# Multimeter1_1.net
KiCad netlist of a schematic drawn in EAGLE
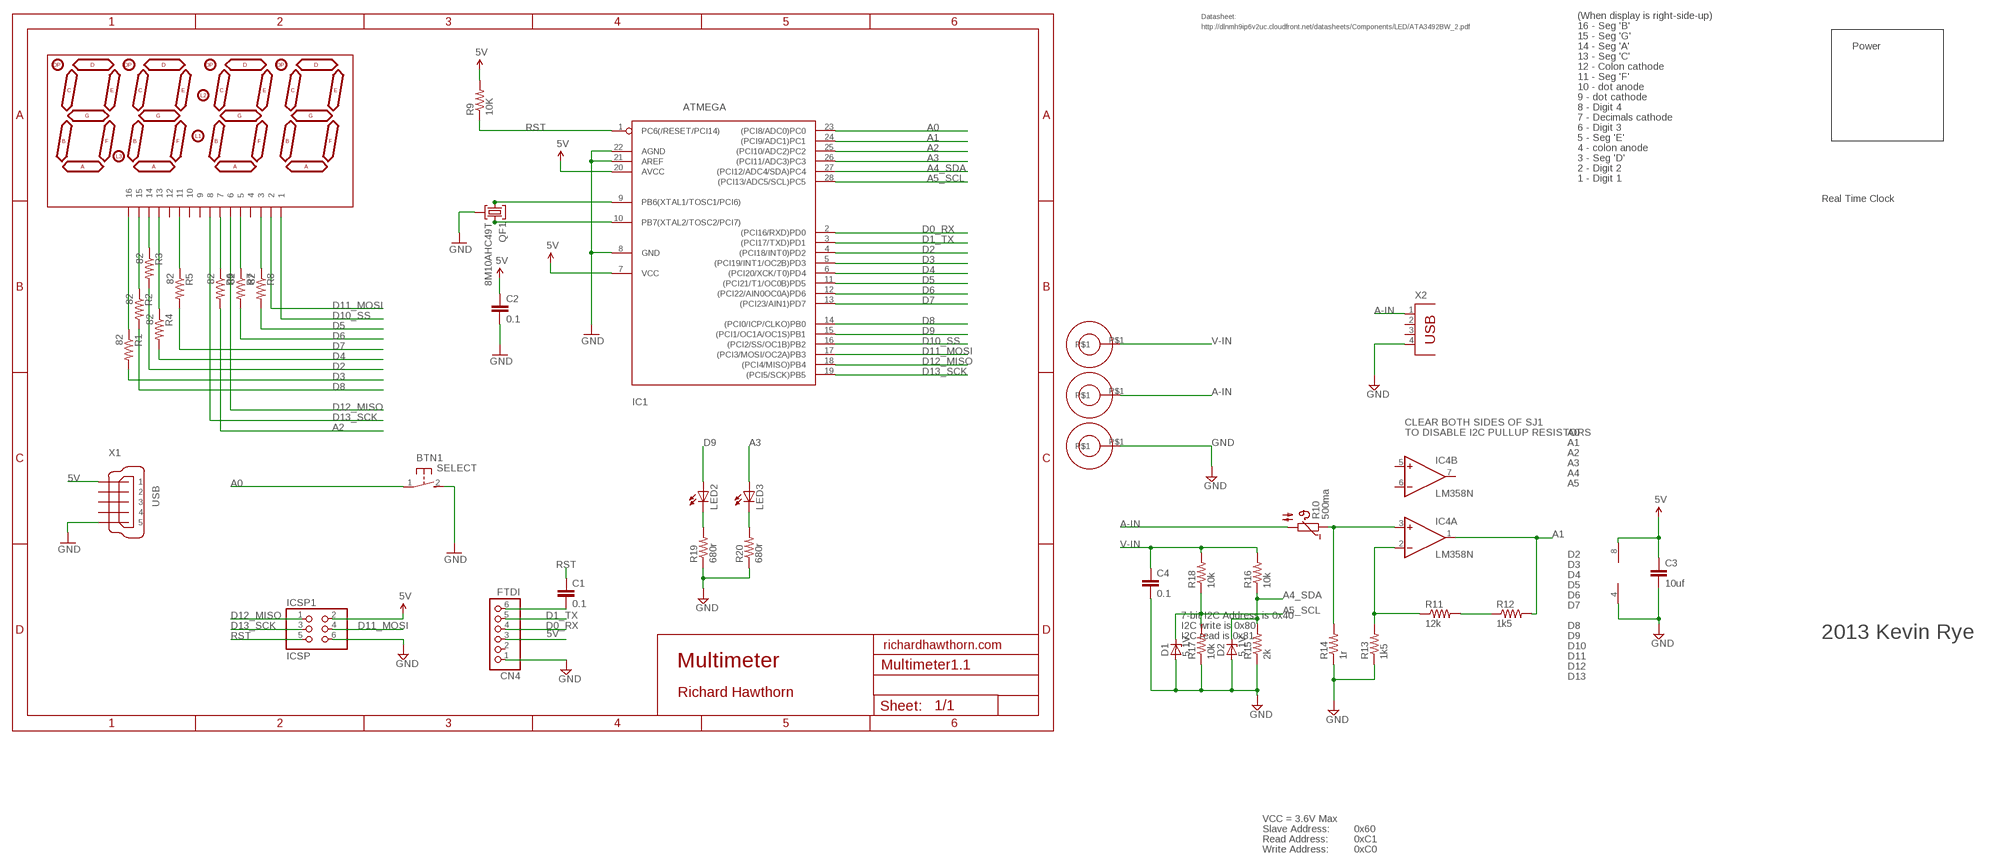
[diagram p0: schematic, sheet 1]

(export (version "E")
  (design (tool "Eeschema 10.0.6"))
  (components
    (comp (ref "BTN1")
      (value "SELECT")
      (footprint "eagle-import:DTS-3")
      (libsource (lib "eagle-import") (part "DTS-3"))
    )
    (comp (ref "C1")
      (value "0.1")
      (footprint "eagle-import:CAP-PTH-SMALL2")
      (libsource (lib "eagle-import") (part "CAPPTH2"))
    )
    (comp (ref "C2")
      (value "0.1")
      (footprint "eagle-import:CAP-PTH-SMALL2")
      (libsource (lib "eagle-import") (part "CAPPTH2"))
    )
    (comp (ref "C3")
      (value "10uf")
      (footprint "eagle-import:CAP-PTH-SMALL2")
      (libsource (lib "eagle-import") (part "CAPPTH2"))
    )
    (comp (ref "C4")
      (value "0.1")
      (footprint "eagle-import:CAP-PTH-SMALL2")
      (libsource (lib "eagle-import") (part "CAPPTH2"))
    )
    (comp (ref "CN4")
      (value "FTDI")
      (footprint "eagle-import:1X06")
      (libsource (lib "eagle-import") (part "PINHD-1X6"))
    )
    (comp (ref "D1")
      (value "5.1V")
      (footprint "eagle-import:DO34Z7")
      (libsource (lib "eagle-import") (part "BZX90"))
    )
    (comp (ref "D2")
      (value "5.1V")
      (footprint "eagle-import:DO34Z7")
      (libsource (lib "eagle-import") (part "BZX90"))
    )
    (comp (ref "IC1")
      (value "ATMEGA")
      (footprint "eagle-import:DIL28-3-ROUND")
      (libsource (lib "eagle-import") (part "ATMEGA168PROUND"))
    )
    (comp (ref "IC4")
      (value "LM358N")
      (footprint "eagle-import:DIL08")
      (libsource (lib "eagle-import") (part "LM358N"))
    )
    (comp (ref "ICSP1")
      (value "ICSP")
      (footprint "eagle-import:2X03")
      (libsource (lib "eagle-import") (part "PINHD-2X3"))
    )
    (comp (ref "LED1")
      (value "7SEG-4DIGIT")
      (footprint "eagle-import:SPARKFUN_7-SEGMENT-4DIGIT")
      (libsource (lib "eagle-import") (part "7SEG-4DIGIT"))
    )
    (comp (ref "LED2")
      (value "LED5MM")
      (footprint "eagle-import:LED5MM")
      (libsource (lib "eagle-import") (part "LED5MM"))
    )
    (comp (ref "LED3")
      (value "LED5MM")
      (footprint "eagle-import:LED5MM")
      (libsource (lib "eagle-import") (part "LED5MM"))
    )
    (comp (ref "QF1")
      (value "8M10AHC49T")
      (footprint "eagle-import:HC49U")
      (libsource (lib "eagle-import") (part "8M10AHC49T"))
    )
    (comp (ref "R1")
      (value "82")
      (footprint "eagle-import:0204_7")
      (libsource (lib "eagle-import") (part "R-US_0204/7"))
    )
    (comp (ref "R2")
      (value "82")
      (footprint "eagle-import:0204_7")
      (libsource (lib "eagle-import") (part "R-US_0204/7"))
    )
    (comp (ref "R3")
      (value "82")
      (footprint "eagle-import:0204_7")
      (libsource (lib "eagle-import") (part "R-US_0204/7"))
    )
    (comp (ref "R4")
      (value "82")
      (footprint "eagle-import:0204_7")
      (libsource (lib "eagle-import") (part "R-US_0204/7"))
    )
    (comp (ref "R5")
      (value "82")
      (footprint "eagle-import:0204_7")
      (libsource (lib "eagle-import") (part "R-US_0204/7"))
    )
    (comp (ref "R6")
      (value "82")
      (footprint "eagle-import:0204_7")
      (libsource (lib "eagle-import") (part "R-US_0204/7"))
    )
    (comp (ref "R7")
      (value "82")
      (footprint "eagle-import:0204_7")
      (libsource (lib "eagle-import") (part "R-US_0204/7"))
    )
    (comp (ref "R8")
      (value "82")
      (footprint "eagle-import:0204_7")
      (libsource (lib "eagle-import") (part "R-US_0204/7"))
    )
    (comp (ref "R9")
      (value "10K")
      (footprint "eagle-import:0204_7")
      (libsource (lib "eagle-import") (part "R-US_0204/7"))
    )
    (comp (ref "R10")
      (value "500ma")
      (footprint "eagle-import:B57164")
      (fields (field (name "MPN") "B57164K474K52"))
      (libsource (lib "eagle-import") (part "B57164"))
    )
    (comp (ref "R11")
      (value "12k")
      (footprint "eagle-import:0204_7")
      (libsource (lib "eagle-import") (part "R-US_0204/7"))
    )
    (comp (ref "R12")
      (value "1k5")
      (footprint "eagle-import:0204_7")
      (libsource (lib "eagle-import") (part "R-US_0204/7"))
    )
    (comp (ref "R13")
      (value "1k5")
      (footprint "eagle-import:0204_7")
      (libsource (lib "eagle-import") (part "R-US_0204/7"))
    )
    (comp (ref "R14")
      (value "1r")
      (footprint "eagle-import:0204_7")
      (libsource (lib "eagle-import") (part "R-US_0204/7"))
    )
    (comp (ref "R15")
      (value "2k")
      (footprint "eagle-import:0204_7")
      (libsource (lib "eagle-import") (part "R-US_0204/7"))
    )
    (comp (ref "R16")
      (value "10k")
      (footprint "eagle-import:0204_7")
      (libsource (lib "eagle-import") (part "R-US_0204/7"))
    )
    (comp (ref "R17")
      (value "10k")
      (footprint "eagle-import:0204_7")
      (libsource (lib "eagle-import") (part "R-US_0204/7"))
    )
    (comp (ref "R18")
      (value "10k")
      (footprint "eagle-import:0204_7")
      (libsource (lib "eagle-import") (part "R-US_0204/7"))
    )
    (comp (ref "R19")
      (value "680r")
      (footprint "eagle-import:0204_7")
      (libsource (lib "eagle-import") (part "R-US_0204/7"))
    )
    (comp (ref "R20")
      (value "680r")
      (footprint "eagle-import:0204_7")
      (libsource (lib "eagle-import") (part "R-US_0204/7"))
    )
    (comp (ref "U$1")
      (value "BANANA")
      (footprint "eagle-import:BANANA")
      (libsource (lib "eagle-import") (part "BANANA"))
    )
    (comp (ref "U$5")
      (value "BANANA")
      (footprint "eagle-import:BANANA")
      (libsource (lib "eagle-import") (part "BANANA"))
    )
    (comp (ref "U$6")
      (value "BANANA")
      (footprint "eagle-import:BANANA")
      (libsource (lib "eagle-import") (part "BANANA"))
    )
    (comp (ref "X1")
      (value "USB")
      (footprint "eagle-import:32005-601")
      (libsource (lib "eagle-import") (part "MINI-USB_SHIELD5P2-32005-601"))
    )
    (comp (ref "X2")
      (value "PN87520")
      (footprint "eagle-import:PN87520")
      (libsource (lib "eagle-import") (part "PN87520"))
    )
  )
  (nets
    (net (code "1") (name "/A-IN") (class "Default")
      (node (ref "R10") (pin "2") (pinfunction "2_2") (pintype "passive"))
      (node (ref "U$5") (pin "P$1") (pinfunction "P$1_P$1") (pintype "bidirectional"))
      (node (ref "X2") (pin "1") (pinfunction "1_1") (pintype "passive"))
    )
    (net (code "2") (name "/A0") (class "Default")
      (node (ref "BTN1") (pin "1") (pinfunction "1_1") (pintype "passive"))
      (node (ref "IC1") (pin "23") (pinfunction "(PCI8/ADC0)PC0_23") (pintype "bidirectional"))
    )
    (net (code "3") (name "/A1") (class "Default")
      (node (ref "IC1") (pin "24") (pinfunction "(PCI9/ADC1)PC1_24") (pintype "bidirectional"))
      (node (ref "IC4") (pin "1") (pinfunction "OUT_1") (pintype "output"))
      (node (ref "R12") (pin "2") (pinfunction "2_2") (pintype "passive"))
    )
    (net (code "4") (name "/A2") (class "Default")
      (node (ref "IC1") (pin "25") (pinfunction "(PCI10/ADC2)PC2_25") (pintype "bidirectional"))
      (node (ref "R6") (pin "2") (pinfunction "2_2") (pintype "passive"))
    )
    (net (code "5") (name "/A3") (class "Default")
      (node (ref "IC1") (pin "26") (pinfunction "(PCI11/ADC3)PC3_26") (pintype "bidirectional"))
      (node (ref "LED3") (pin "A") (pinfunction "A_A") (pintype "passive"))
    )
    (net (code "6") (name "/A4_SDA") (class "Default")
      (node (ref "D2") (pin "C") (pinfunction "C_C") (pintype "passive"))
      (node (ref "IC1") (pin "27") (pinfunction "(PCI12/ADC4/SDA)PC4_27") (pintype "bidirectional"))
      (node (ref "R15") (pin "2") (pinfunction "2_2") (pintype "passive"))
      (node (ref "R16") (pin "1") (pinfunction "1_1") (pintype "passive"))
    )
    (net (code "7") (name "/A5_SCL") (class "Default")
      (node (ref "D1") (pin "C") (pinfunction "C_C") (pintype "passive"))
      (node (ref "IC1") (pin "28") (pinfunction "(PCI13/ADC5/SCL)PC5_28") (pintype "bidirectional"))
      (node (ref "R17") (pin "2") (pinfunction "2_2") (pintype "passive"))
      (node (ref "R18") (pin "1") (pinfunction "1_1") (pintype "passive"))
    )
    (net (code "8") (name "/D0_RX") (class "Default")
      (node (ref "CN4") (pin "4") (pinfunction "4_4") (pintype "passive"))
      (node (ref "IC1") (pin "2") (pinfunction "(PCI16/RXD)PD0_2") (pintype "bidirectional"))
    )
    (net (code "9") (name "/D1_TX") (class "Default")
      (node (ref "CN4") (pin "5") (pinfunction "5_5") (pintype "passive"))
      (node (ref "IC1") (pin "3") (pinfunction "(PCI17/TXD)PD1_3") (pintype "bidirectional"))
    )
    (net (code "10") (name "/D2") (class "Default")
      (node (ref "IC1") (pin "4") (pinfunction "(PCI18/INT0)PD2_4") (pintype "bidirectional"))
      (node (ref "R3") (pin "2") (pinfunction "2_2") (pintype "passive"))
    )
    (net (code "11") (name "/D3") (class "Default")
      (node (ref "IC1") (pin "5") (pinfunction "(PCI19/INT1/OC2B)PD3_5") (pintype "bidirectional"))
      (node (ref "R1") (pin "2") (pinfunction "2_2") (pintype "passive"))
    )
    (net (code "12") (name "/D4") (class "Default")
      (node (ref "IC1") (pin "6") (pinfunction "(PCI20/XCK/T0)PD4_6") (pintype "bidirectional"))
      (node (ref "R4") (pin "2") (pinfunction "2_2") (pintype "passive"))
    )
    (net (code "13") (name "/D5") (class "Default")
      (node (ref "IC1") (pin "11") (pinfunction "(PCI21/T1/OC0B)PD5_11") (pintype "bidirectional"))
      (node (ref "R8") (pin "2") (pinfunction "2_2") (pintype "passive"))
    )
    (net (code "14") (name "/D6") (class "Default")
      (node (ref "IC1") (pin "12") (pinfunction "(PCI22/AIN0OC0A)PD6_12") (pintype "bidirectional"))
      (node (ref "R7") (pin "2") (pinfunction "2_2") (pintype "passive"))
    )
    (net (code "15") (name "/D7") (class "Default")
      (node (ref "IC1") (pin "13") (pinfunction "(PCI23/AIN1)PD7_13") (pintype "bidirectional"))
      (node (ref "R5") (pin "2") (pinfunction "2_2") (pintype "passive"))
    )
    (net (code "16") (name "/D8") (class "Default")
      (node (ref "IC1") (pin "14") (pinfunction "(PCI0/ICP/CLKO)PB0_14") (pintype "bidirectional"))
      (node (ref "R2") (pin "2") (pinfunction "2_2") (pintype "passive"))
    )
    (net (code "17") (name "/D9") (class "Default")
      (node (ref "IC1") (pin "15") (pinfunction "(PCI1/OC1A/OC1S)PB1_15") (pintype "bidirectional"))
      (node (ref "LED2") (pin "A") (pinfunction "A_A") (pintype "passive"))
    )
    (net (code "18") (name "/D10_SS") (class "Default")
      (node (ref "IC1") (pin "16") (pinfunction "(PCI2/SS/OC1B)PB2_16") (pintype "bidirectional"))
      (node (ref "LED1") (pin "1") (pinfunction "1_1") (pintype "bidirectional"))
    )
    (net (code "19") (name "/D11_MOSI") (class "Default")
      (node (ref "IC1") (pin "17") (pinfunction "(PCI3/MOSI/OC2A)PB3_17") (pintype "bidirectional"))
      (node (ref "ICSP1") (pin "4") (pinfunction "4_4") (pintype "passive"))
      (node (ref "LED1") (pin "2") (pinfunction "2_2") (pintype "bidirectional"))
    )
    (net (code "20") (name "/D12_MISO") (class "Default")
      (node (ref "IC1") (pin "18") (pinfunction "(PCI4/MISO)PB4_18") (pintype "bidirectional"))
      (node (ref "ICSP1") (pin "1") (pinfunction "1_1") (pintype "passive"))
      (node (ref "LED1") (pin "6") (pinfunction "6_6") (pintype "bidirectional"))
    )
    (net (code "21") (name "/D13_SCK") (class "Default")
      (node (ref "IC1") (pin "19") (pinfunction "(PCI5/SCK)PB5_19") (pintype "bidirectional"))
      (node (ref "ICSP1") (pin "3") (pinfunction "3_3") (pintype "passive"))
      (node (ref "LED1") (pin "8") (pinfunction "8_8") (pintype "bidirectional"))
    )
    (net (code "22") (name "/RST") (class "Default")
      (node (ref "C1") (pin "1") (pinfunction "1_1") (pintype "passive"))
      (node (ref "IC1") (pin "1") (pinfunction "PC6(/RESET/PCI14)_1") (pintype "bidirectional"))
      (node (ref "ICSP1") (pin "5") (pinfunction "5_5") (pintype "passive"))
      (node (ref "R9") (pin "1") (pinfunction "1_1") (pintype "passive"))
    )
    (net (code "23") (name "/V-IN") (class "Default")
      (node (ref "C4") (pin "1") (pinfunction "1_1") (pintype "passive"))
      (node (ref "R16") (pin "2") (pinfunction "2_2") (pintype "passive"))
      (node (ref "R18") (pin "2") (pinfunction "2_2") (pintype "passive"))
      (node (ref "U$1") (pin "P$1") (pinfunction "P$1_P$1") (pintype "bidirectional"))
    )
    (net (code "24") (name "5V") (class "Default")
      (node (ref "C2") (pin "1") (pinfunction "1_1") (pintype "passive"))
      (node (ref "C3") (pin "1") (pinfunction "1_1") (pintype "passive"))
      (node (ref "CN4") (pin "3") (pinfunction "3_3") (pintype "passive"))
      (node (ref "IC1") (pin "20") (pinfunction "AVCC_20") (pintype "bidirectional"))
      (node (ref "IC1") (pin "7") (pinfunction "VCC_7") (pintype "bidirectional"))
      (node (ref "IC4") (pin "8") (pinfunction "V+_8") (pintype "power_in"))
      (node (ref "ICSP1") (pin "2") (pinfunction "2_2") (pintype "passive"))
      (node (ref "R9") (pin "2") (pinfunction "2_2") (pintype "passive"))
      (node (ref "X1") (pin "1") (pinfunction "1_1") (pintype "passive"))
    )
    (net (code "25") (name "GND") (class "Default")
      (node (ref "BTN1") (pin "2") (pinfunction "2_2") (pintype "passive"))
      (node (ref "C2") (pin "2") (pinfunction "2_2") (pintype "passive"))
      (node (ref "C3") (pin "2") (pinfunction "2_2") (pintype "passive"))
      (node (ref "C4") (pin "2") (pinfunction "2_2") (pintype "passive"))
      (node (ref "CN4") (pin "1") (pinfunction "1_1") (pintype "passive"))
      (node (ref "D1") (pin "A") (pinfunction "A_A") (pintype "passive"))
      (node (ref "D2") (pin "A") (pinfunction "A_A") (pintype "passive"))
      (node (ref "IC1") (pin "21") (pinfunction "AREF_21") (pintype "bidirectional"))
      (node (ref "IC1") (pin "22") (pinfunction "AGND_22") (pintype "bidirectional"))
      (node (ref "IC1") (pin "8") (pinfunction "GND_8") (pintype "bidirectional"))
      (node (ref "IC4") (pin "4") (pinfunction "V-_4") (pintype "power_in"))
      (node (ref "ICSP1") (pin "6") (pinfunction "6_6") (pintype "passive"))
      (node (ref "QF1") (pin "2") (pinfunction "2_2") (pintype "passive"))
      (node (ref "R13") (pin "1") (pinfunction "1_1") (pintype "passive"))
      (node (ref "R14") (pin "1") (pinfunction "1_1") (pintype "passive"))
      (node (ref "R15") (pin "1") (pinfunction "1_1") (pintype "passive"))
      (node (ref "R17") (pin "1") (pinfunction "1_1") (pintype "passive"))
      (node (ref "R19") (pin "1") (pinfunction "1_1") (pintype "passive"))
      (node (ref "R20") (pin "1") (pinfunction "1_1") (pintype "passive"))
      (node (ref "U$6") (pin "P$1") (pinfunction "P$1_P$1") (pintype "bidirectional"))
      (node (ref "X1") (pin "5") (pinfunction "5_5") (pintype "passive"))
      (node (ref "X2") (pin "4") (pinfunction "4_4") (pintype "passive"))
    )
    (net (code "26") (name "Net-(C1-Pad2)") (class "Default")
      (node (ref "C1") (pin "2") (pinfunction "2_2") (pintype "passive"))
      (node (ref "CN4") (pin "6") (pinfunction "6_6") (pintype "passive"))
    )
    (net (code "27") (name "Net-(IC1-PB6(XTAL1{slash}TOSC1{slash}PCI6))") (class "Default")
      (node (ref "IC1") (pin "9") (pinfunction "PB6(XTAL1/TOSC1/PCI6)_9") (pintype "bidirectional"))
      (node (ref "QF1") (pin "1") (pinfunction "1_1") (pintype "passive"))
    )
    (net (code "28") (name "Net-(IC1-PB7(XTAL2{slash}TOSC2{slash}PCI7))") (class "Default")
      (node (ref "IC1") (pin "10") (pinfunction "PB7(XTAL2/TOSC2/PCI7)_10") (pintype "bidirectional"))
      (node (ref "QF1") (pin "3") (pinfunction "3_3") (pintype "passive"))
    )
    (net (code "29") (name "Net-(IC4A-+IN)") (class "Default")
      (node (ref "IC4") (pin "3") (pinfunction "+IN_3") (pintype "input"))
      (node (ref "R10") (pin "1") (pinfunction "1_1") (pintype "passive"))
      (node (ref "R14") (pin "2") (pinfunction "2_2") (pintype "passive"))
    )
    (net (code "30") (name "Net-(IC4A--IN)") (class "Default")
      (node (ref "IC4") (pin "2") (pinfunction "-IN_2") (pintype "input"))
      (node (ref "R11") (pin "1") (pinfunction "1_1") (pintype "passive"))
      (node (ref "R13") (pin "2") (pinfunction "2_2") (pintype "passive"))
    )
    (net (code "31") (name "Net-(LED1-Pad3)") (class "Default")
      (node (ref "LED1") (pin "3") (pinfunction "3_3") (pintype "bidirectional"))
      (node (ref "R8") (pin "1") (pinfunction "1_1") (pintype "passive"))
    )
    (net (code "32") (name "Net-(LED1-Pad5)") (class "Default")
      (node (ref "LED1") (pin "5") (pinfunction "5_5") (pintype "bidirectional"))
      (node (ref "R7") (pin "1") (pinfunction "1_1") (pintype "passive"))
    )
    (net (code "33") (name "Net-(LED1-Pad7)") (class "Default")
      (node (ref "LED1") (pin "7") (pinfunction "7_7") (pintype "bidirectional"))
      (node (ref "R6") (pin "1") (pinfunction "1_1") (pintype "passive"))
    )
    (net (code "34") (name "Net-(LED1-Pad11)") (class "Default")
      (node (ref "LED1") (pin "11") (pinfunction "11_11") (pintype "bidirectional"))
      (node (ref "R5") (pin "1") (pinfunction "1_1") (pintype "passive"))
    )
    (net (code "35") (name "Net-(LED1-Pad13)") (class "Default")
      (node (ref "LED1") (pin "13") (pinfunction "13_13") (pintype "bidirectional"))
      (node (ref "R4") (pin "1") (pinfunction "1_1") (pintype "passive"))
    )
    (net (code "36") (name "Net-(LED1-Pad14)") (class "Default")
      (node (ref "LED1") (pin "14") (pinfunction "14_14") (pintype "bidirectional"))
      (node (ref "R3") (pin "1") (pinfunction "1_1") (pintype "passive"))
    )
    (net (code "37") (name "Net-(LED1-Pad15)") (class "Default")
      (node (ref "LED1") (pin "15") (pinfunction "15_15") (pintype "bidirectional"))
      (node (ref "R2") (pin "1") (pinfunction "1_1") (pintype "passive"))
    )
    (net (code "38") (name "Net-(LED1-Pad16)") (class "Default")
      (node (ref "LED1") (pin "16") (pinfunction "16_16") (pintype "bidirectional"))
      (node (ref "R1") (pin "1") (pinfunction "1_1") (pintype "passive"))
    )
    (net (code "39") (name "Net-(LED2-C)") (class "Default")
      (node (ref "LED2") (pin "K") (pinfunction "C_K") (pintype "passive"))
      (node (ref "R19") (pin "2") (pinfunction "2_2") (pintype "passive"))
    )
    (net (code "40") (name "Net-(LED3-C)") (class "Default")
      (node (ref "LED3") (pin "K") (pinfunction "C_K") (pintype "passive"))
      (node (ref "R20") (pin "2") (pinfunction "2_2") (pintype "passive"))
    )
    (net (code "41") (name "Net-(R11-Pad2)") (class "Default")
      (node (ref "R11") (pin "2") (pinfunction "2_2") (pintype "passive"))
      (node (ref "R12") (pin "1") (pinfunction "1_1") (pintype "passive"))
    )
    (net (code "42") (name "unconnected-(CN4-Pad2)") (class "Default")
      (node (ref "CN4") (pin "2") (pinfunction "2_2") (pintype "passive"))
    )
    (net (code "43") (name "unconnected-(IC4B-+IN-Pad5)") (class "Default")
      (node (ref "IC4") (pin "5") (pinfunction "+IN_5") (pintype "input"))
    )
    (net (code "44") (name "unconnected-(IC4B--IN-Pad6)") (class "Default")
      (node (ref "IC4") (pin "6") (pinfunction "-IN_6") (pintype "input"))
    )
    (net (code "45") (name "unconnected-(IC4B-OUT-Pad7)") (class "Default")
      (node (ref "IC4") (pin "7") (pinfunction "OUT_7") (pintype "output"))
    )
    (net (code "46") (name "unconnected-(LED1-Pad4)") (class "Default")
      (node (ref "LED1") (pin "4") (pinfunction "4_4") (pintype "bidirectional"))
    )
    (net (code "47") (name "unconnected-(LED1-Pad9)") (class "Default")
      (node (ref "LED1") (pin "9") (pinfunction "9_9") (pintype "bidirectional"))
    )
    (net (code "48") (name "unconnected-(LED1-Pad10)") (class "Default")
      (node (ref "LED1") (pin "10") (pinfunction "10_10") (pintype "bidirectional"))
    )
    (net (code "49") (name "unconnected-(LED1-Pad12)") (class "Default")
      (node (ref "LED1") (pin "12") (pinfunction "12_12") (pintype "bidirectional"))
    )
    (net (code "50") (name "unconnected-(X1-Pad2)") (class "Default")
      (node (ref "X1") (pin "2") (pinfunction "2_2") (pintype "passive"))
    )
    (net (code "51") (name "unconnected-(X1-Pad3)") (class "Default")
      (node (ref "X1") (pin "3") (pinfunction "3_3") (pintype "passive"))
    )
    (net (code "52") (name "unconnected-(X1-Pad4)") (class "Default")
      (node (ref "X1") (pin "4") (pinfunction "4_4") (pintype "passive"))
    )
    (net (code "53") (name "unconnected-(X2-Pad2)") (class "Default")
      (node (ref "X2") (pin "2") (pinfunction "2_2") (pintype "passive"))
    )
    (net (code "54") (name "unconnected-(X2-Pad3)") (class "Default")
      (node (ref "X2") (pin "3") (pinfunction "3_3") (pintype "passive"))
    )
  )
)
